# 7f_-_CAN.net
KiCad netlist of a schematic drawn in Altium Designer
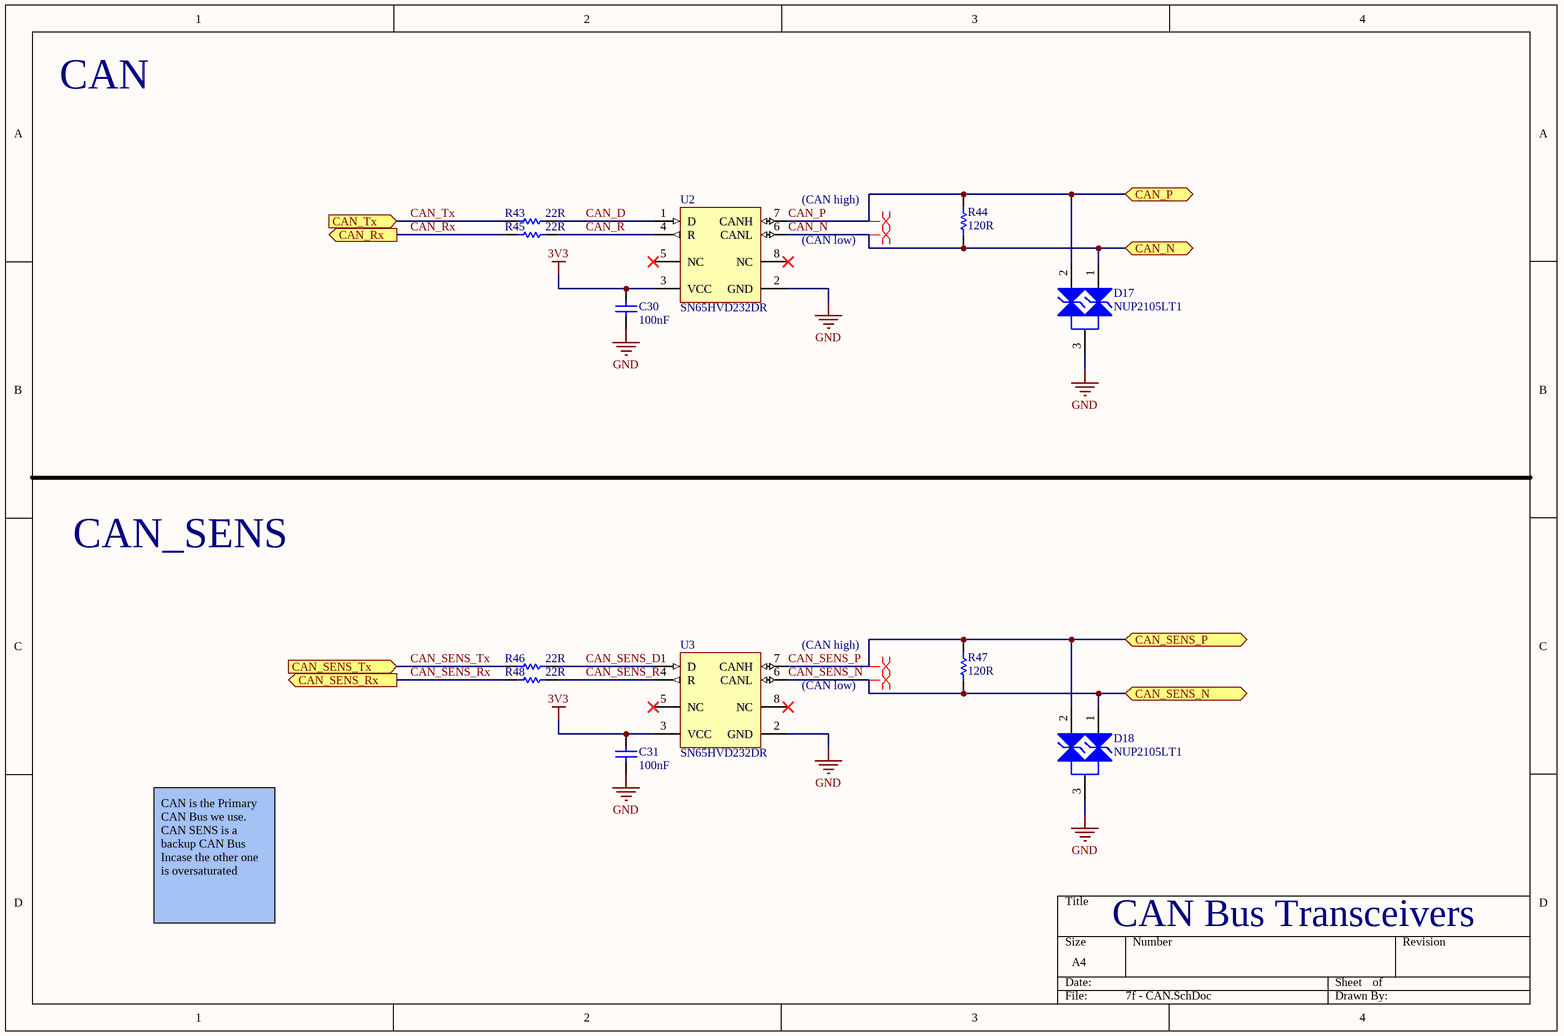
[diagram p0: 7f - CAN.SchDoc]

(export (version "E")
  (design (tool "Eeschema 10.0.6"))
  (components
    (comp (ref "C30")
      (value "100nF")
      (footprint "1608[0603]")
      (description "Capacitor")
      (fields (field (name "Comment") "Cap") (field (name "PUBLISHER") "Altium Limited"))
      (libsource (lib "Miscellaneous Devices") (part "Cap"))
    )
    (comp (ref "C31")
      (value "100nF")
      (footprint "1608[0603]")
      (description "Capacitor")
      (fields (field (name "Comment") "Cap") (field (name "PUBLISHER") "Altium Limited"))
      (libsource (lib "Miscellaneous Devices") (part "Cap"))
    )
    (comp (ref "D17")
      (value "NUP2105LT1")
      (footprint "ONSC-SOT-23-3-318-08_V")
      (description "Dual Line CAN Bus Protector, 3-Pin SOT-23, Tape and Reel")
      (fields (field (name "MANUFACTURER") "On Semiconductor"))
      (libsource (lib "Altium Content Vault") (part "ONSC-NUP21X5X-SOT-23-3-318-08"))
    )
    (comp (ref "D18")
      (value "NUP2105LT1")
      (footprint "ONSC-SOT-23-3-318-08_V")
      (description "Dual Line CAN Bus Protector, 3-Pin SOT-23, Tape and Reel")
      (fields (field (name "MANUFACTURER") "On Semiconductor"))
      (libsource (lib "Altium Content Vault") (part "ONSC-NUP21X5X-SOT-23-3-318-08"))
    )
    (comp (ref "R43")
      (value "22R")
      (footprint "1608[0603]")
      (description "Resistor")
      (fields (field (name "Comment") "Res1") (field (name "PUBLISHER") "Altium Limited"))
      (libsource (lib "Miscellaneous Devices") (part "Res1"))
    )
    (comp (ref "R44")
      (value "120R")
      (footprint "1608[0603]")
      (description "Resistor")
      (fields (field (name "Comment") "Res1") (field (name "PUBLISHER") "Altium Limited"))
      (libsource (lib "Miscellaneous Devices") (part "Res1"))
    )
    (comp (ref "R45")
      (value "22R")
      (footprint "1608[0603]")
      (description "Resistor")
      (fields (field (name "Comment") "Res1") (field (name "PUBLISHER") "Altium Limited"))
      (libsource (lib "Miscellaneous Devices") (part "Res1"))
    )
    (comp (ref "R46")
      (value "22R")
      (footprint "1608[0603]")
      (description "Resistor")
      (fields (field (name "Comment") "Res1") (field (name "PUBLISHER") "Altium Limited"))
      (libsource (lib "Miscellaneous Devices") (part "Res1"))
    )
    (comp (ref "R47")
      (value "120R")
      (footprint "1608[0603]")
      (description "Resistor")
      (fields (field (name "Comment") "Res1") (field (name "PUBLISHER") "Altium Limited"))
      (libsource (lib "Miscellaneous Devices") (part "Res1"))
    )
    (comp (ref "R48")
      (value "22R")
      (footprint "1608[0603]")
      (description "Resistor")
      (fields (field (name "Comment") "Res1") (field (name "PUBLISHER") "Altium Limited"))
      (libsource (lib "Miscellaneous Devices") (part "Res1"))
    )
    (comp (ref "U2")
      (value "SN65HVD232DR")
      (footprint "D0008A_M")
      (description "3.3 V Can Transceiver, 17 mA, -40 to 85 degC, 8-pin SOIC (D), Green (RoHS & no Sb/Br)")
      (fields (field (name "MANUFACTURER") "Texas Instruments"))
      (libsource (lib "Altium Content Vault") (part "TI-SN65HVD232-SOIC_D-8"))
    )
    (comp (ref "U3")
      (value "SN65HVD232DR")
      (footprint "D0008A_M")
      (description "3.3 V Can Transceiver, 17 mA, -40 to 85 degC, 8-pin SOIC (D), Green (RoHS & no Sb/Br)")
      (fields (field (name "MANUFACTURER") "Texas Instruments"))
      (libsource (lib "Altium Content Vault") (part "TI-SN65HVD232-SOIC_D-8"))
    )
  )
  (nets
    (net (code "1") (name "/CAN_D") (class "Default")
      (node (ref "R43") (pin "2") (pinfunction "2_2") (pintype "passive"))
      (node (ref "U2") (pin "1") (pinfunction "D_1") (pintype "input"))
    )
    (net (code "2") (name "/CAN_N") (class "Default")
      (node (ref "D17") (pin "1") (pinfunction "K_1") (pintype "passive"))
      (node (ref "R44") (pin "1") (pinfunction "1_1") (pintype "passive"))
      (node (ref "U2") (pin "6") (pinfunction "CANL_6") (pintype "bidirectional"))
    )
    (net (code "3") (name "/CAN_P") (class "Default")
      (node (ref "D17") (pin "2") (pinfunction "K_2") (pintype "passive"))
      (node (ref "R44") (pin "2") (pinfunction "2_2") (pintype "passive"))
      (node (ref "U2") (pin "7") (pinfunction "CANH_7") (pintype "bidirectional"))
    )
    (net (code "4") (name "/CAN_R") (class "Default")
      (node (ref "R45") (pin "2") (pinfunction "2_2") (pintype "passive"))
      (node (ref "U2") (pin "4") (pinfunction "R_4") (pintype "output"))
    )
    (net (code "5") (name "/CAN_Rx") (class "Default")
      (node (ref "R45") (pin "1") (pinfunction "1_1") (pintype "passive"))
    )
    (net (code "6") (name "/CAN_SENS_D") (class "Default")
      (node (ref "R46") (pin "2") (pinfunction "2_2") (pintype "passive"))
      (node (ref "U3") (pin "1") (pinfunction "D_1") (pintype "input"))
    )
    (net (code "7") (name "/CAN_SENS_N") (class "Default")
      (node (ref "D18") (pin "1") (pinfunction "K_1") (pintype "passive"))
      (node (ref "R47") (pin "1") (pinfunction "1_1") (pintype "passive"))
      (node (ref "U3") (pin "6") (pinfunction "CANL_6") (pintype "bidirectional"))
    )
    (net (code "8") (name "/CAN_SENS_P") (class "Default")
      (node (ref "D18") (pin "2") (pinfunction "K_2") (pintype "passive"))
      (node (ref "R47") (pin "2") (pinfunction "2_2") (pintype "passive"))
      (node (ref "U3") (pin "7") (pinfunction "CANH_7") (pintype "bidirectional"))
    )
    (net (code "9") (name "/CAN_SENS_R") (class "Default")
      (node (ref "R48") (pin "2") (pinfunction "2_2") (pintype "passive"))
      (node (ref "U3") (pin "4") (pinfunction "R_4") (pintype "output"))
    )
    (net (code "10") (name "/CAN_SENS_Rx") (class "Default")
      (node (ref "R48") (pin "1") (pinfunction "1_1") (pintype "passive"))
    )
    (net (code "11") (name "/CAN_SENS_Tx") (class "Default")
      (node (ref "R46") (pin "1") (pinfunction "1_1") (pintype "passive"))
    )
    (net (code "12") (name "/CAN_Tx") (class "Default")
      (node (ref "R43") (pin "1") (pinfunction "1_1") (pintype "passive"))
    )
    (net (code "13") (name "3V3") (class "Default")
      (node (ref "C30") (pin "2") (pinfunction "2_2") (pintype "passive"))
      (node (ref "C31") (pin "2") (pinfunction "2_2") (pintype "passive"))
      (node (ref "U2") (pin "3") (pinfunction "VCC_3") (pintype "power_in"))
      (node (ref "U3") (pin "3") (pinfunction "VCC_3") (pintype "power_in"))
    )
    (net (code "14") (name "GND") (class "Default")
      (node (ref "C30") (pin "1") (pinfunction "1_1") (pintype "passive"))
      (node (ref "C31") (pin "1") (pinfunction "1_1") (pintype "passive"))
      (node (ref "D17") (pin "3") (pinfunction "K_3") (pintype "passive"))
      (node (ref "D18") (pin "3") (pinfunction "K_3") (pintype "passive"))
      (node (ref "U2") (pin "2") (pinfunction "GND_2") (pintype "power_in"))
      (node (ref "U3") (pin "2") (pinfunction "GND_2") (pintype "power_in"))
    )
    (net (code "15") (name "unconnected-(U2-NC-Pad5)") (class "Default")
      (node (ref "U2") (pin "5") (pinfunction "NC_5") (pintype "passive+no_connect"))
    )
    (net (code "16") (name "unconnected-(U2-NC-Pad8)") (class "Default")
      (node (ref "U2") (pin "8") (pinfunction "NC_8") (pintype "passive+no_connect"))
    )
    (net (code "17") (name "unconnected-(U3-NC-Pad5)") (class "Default")
      (node (ref "U3") (pin "5") (pinfunction "NC_5") (pintype "passive+no_connect"))
    )
    (net (code "18") (name "unconnected-(U3-NC-Pad8)") (class "Default")
      (node (ref "U3") (pin "8") (pinfunction "NC_8") (pintype "passive+no_connect"))
    )
  )
)
